# DAC.net
KiCad netlist of a schematic drawn in Altium Designer
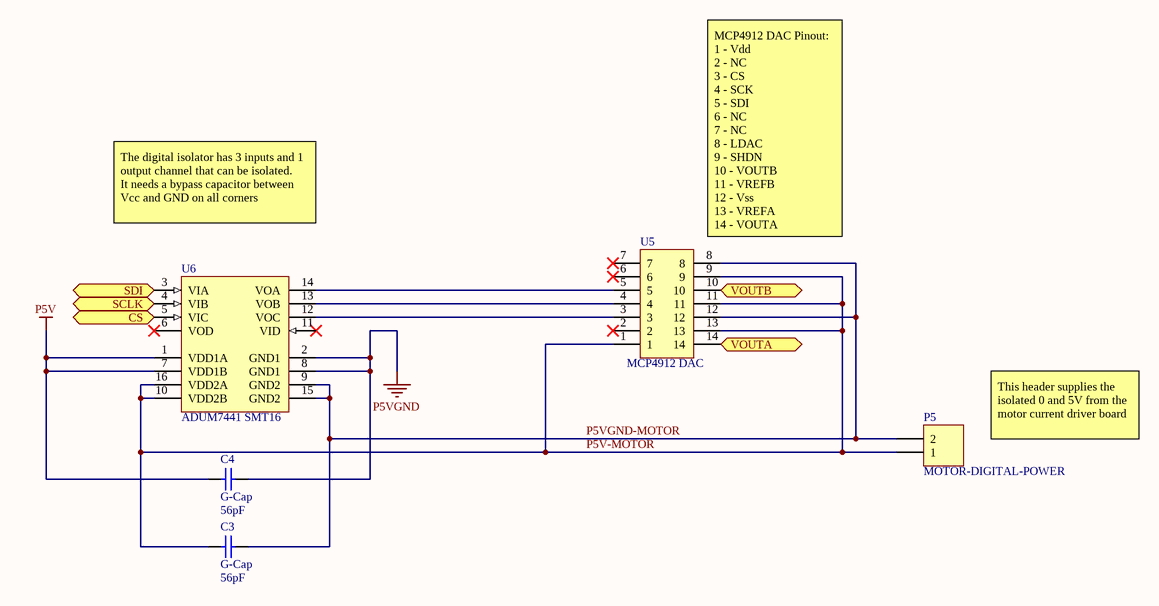
[diagram p0: DAC.SchDoc]

(export (version "E")
  (design (tool "Eeschema 10.0.6"))
  (components
    (comp (ref "C3")
      (value "G-Cap")
      (footprint "Cap2.54mm_LGE1.0")
      (description "capacitor (specify value)")
      (fields (field (name "ALTIUM_VALUE") "56pF") (field (name "PUBLISHER") "Altium Limited"))
      (libsource (lib "PartsDatabaseV13p4") (part "G-Cap"))
    )
    (comp (ref "C4")
      (value "G-Cap")
      (footprint "Cap2.54mm_LGE1.0")
      (description "capacitor (specify value)")
      (fields (field (name "ALTIUM_VALUE") "56pF") (field (name "PUBLISHER") "Altium Limited"))
      (libsource (lib "PartsDatabaseV13p4") (part "G-Cap"))
    )
    (comp (ref "P5")
      (value "MOTOR-DIGITAL-POWER")
      (footprint "HDR1X2_LGE1.0")
      (description "Header, 2-Pin")
      (fields (field (name "PUBLISHER") "Altium Limited"))
      (libsource (lib "PartsDatabaseV13p4") (part "C-Hdr1x2"))
    )
    (comp (ref "U5")
      (value "MCP4912 DAC")
      (footprint "ISDIP14_LGE1.0")
      (description "DAC")
      (fields (field (name "PUBLISHER") "Altium Limited"))
      (libsource (lib "PartsDatabaseV13p4") (part "G-DIP14"))
    )
    (comp (ref "U6")
      (value "ADUM7441 SMT16")
      (footprint "ADUM7441")
      (fields (field (name "MANUFACTURER") "Analog Devices") (field (name "PARTNUMBER") "ADUM7441CRQZ"))
      (libsource (lib "Analog Devices Interface and Isolation Digital Isolators") (part "ADUM7441CRQZ"))
    )
  )
  (nets
    (net (code "1") (name "/CS") (class "Default")
      (node (ref "U6") (pin "5") (pinfunction "VIC_5") (pintype "input"))
    )
    (net (code "2") (name "/P5V-MOTOR") (class "Default")
      (node (ref "C3") (pin "1") (pinfunction "1_1") (pintype "passive"))
      (node (ref "P5") (pin "1") (pinfunction "1_1") (pintype "passive"))
      (node (ref "U5") (pin "1") (pinfunction "1_1") (pintype "passive"))
      (node (ref "U5") (pin "11") (pinfunction "11_11") (pintype "passive"))
      (node (ref "U5") (pin "13") (pinfunction "13_13") (pintype "passive"))
      (node (ref "U5") (pin "9") (pinfunction "9_9") (pintype "passive"))
      (node (ref "U6") (pin "10") (pinfunction "VDD2B_10") (pintype "power_in"))
      (node (ref "U6") (pin "16") (pinfunction "VDD2A_16") (pintype "power_in"))
    )
    (net (code "3") (name "/P5VGND-MOTOR") (class "Default")
      (node (ref "C3") (pin "2") (pinfunction "2_2") (pintype "passive"))
      (node (ref "P5") (pin "2") (pinfunction "2_2") (pintype "passive"))
      (node (ref "U5") (pin "12") (pinfunction "12_12") (pintype "passive"))
      (node (ref "U5") (pin "8") (pinfunction "8_8") (pintype "passive"))
      (node (ref "U6") (pin "15") (pinfunction "GND2_15") (pintype "power_in"))
      (node (ref "U6") (pin "9") (pinfunction "GND2_9") (pintype "power_in"))
    )
    (net (code "4") (name "/SCLK") (class "Default")
      (node (ref "U6") (pin "4") (pinfunction "VIB_4") (pintype "input"))
    )
    (net (code "5") (name "/SDI") (class "Default")
      (node (ref "U6") (pin "3") (pinfunction "VIA_3") (pintype "input"))
    )
    (net (code "6") (name "/VOUTA") (class "Default")
      (node (ref "U5") (pin "14") (pinfunction "14_14") (pintype "passive"))
    )
    (net (code "7") (name "/VOUTB") (class "Default")
      (node (ref "U5") (pin "10") (pinfunction "10_10") (pintype "passive"))
    )
    (net (code "8") (name "Net-(U6-VOA)") (class "Default")
      (node (ref "U5") (pin "5") (pinfunction "5_5") (pintype "passive"))
      (node (ref "U6") (pin "14") (pinfunction "VOA_14") (pintype "tri_state"))
    )
    (net (code "9") (name "Net-(U6-VOB)") (class "Default")
      (node (ref "U5") (pin "4") (pinfunction "4_4") (pintype "passive"))
      (node (ref "U6") (pin "13") (pinfunction "VOB_13") (pintype "tri_state"))
    )
    (net (code "10") (name "Net-(U6-VOC)") (class "Default")
      (node (ref "U5") (pin "3") (pinfunction "3_3") (pintype "passive"))
      (node (ref "U6") (pin "12") (pinfunction "VOC_12") (pintype "tri_state"))
    )
    (net (code "11") (name "P5V") (class "Default")
      (node (ref "C4") (pin "1") (pinfunction "1_1") (pintype "passive"))
      (node (ref "U6") (pin "1") (pinfunction "VDD1A_1") (pintype "power_in"))
      (node (ref "U6") (pin "7") (pinfunction "VDD1B_7") (pintype "power_in"))
    )
    (net (code "12") (name "P5VGND") (class "Default")
      (node (ref "C4") (pin "2") (pinfunction "2_2") (pintype "passive"))
      (node (ref "U6") (pin "2") (pinfunction "GND1_2") (pintype "power_in"))
      (node (ref "U6") (pin "8") (pinfunction "GND1_8") (pintype "power_in"))
    )
    (net (code "13") (name "unconnected-(U5-Pad2)") (class "Default")
      (node (ref "U5") (pin "2") (pinfunction "2_2") (pintype "passive+no_connect"))
    )
    (net (code "14") (name "unconnected-(U5-Pad6)") (class "Default")
      (node (ref "U5") (pin "6") (pinfunction "6_6") (pintype "passive+no_connect"))
    )
    (net (code "15") (name "unconnected-(U5-Pad7)") (class "Default")
      (node (ref "U5") (pin "7") (pinfunction "7_7") (pintype "passive+no_connect"))
    )
    (net (code "16") (name "unconnected-(U6-VID-Pad11)") (class "Default")
      (node (ref "U6") (pin "11") (pinfunction "VID_11") (pintype "input+no_connect"))
    )
    (net (code "17") (name "unconnected-(U6-VOD-Pad6)") (class "Default")
      (node (ref "U6") (pin "6") (pinfunction "VOD_6") (pintype "tri_state+no_connect"))
    )
  )
)
